# PCB-ARD-MMBOS.net
KiCad netlist of a schematic drawn in EAGLE
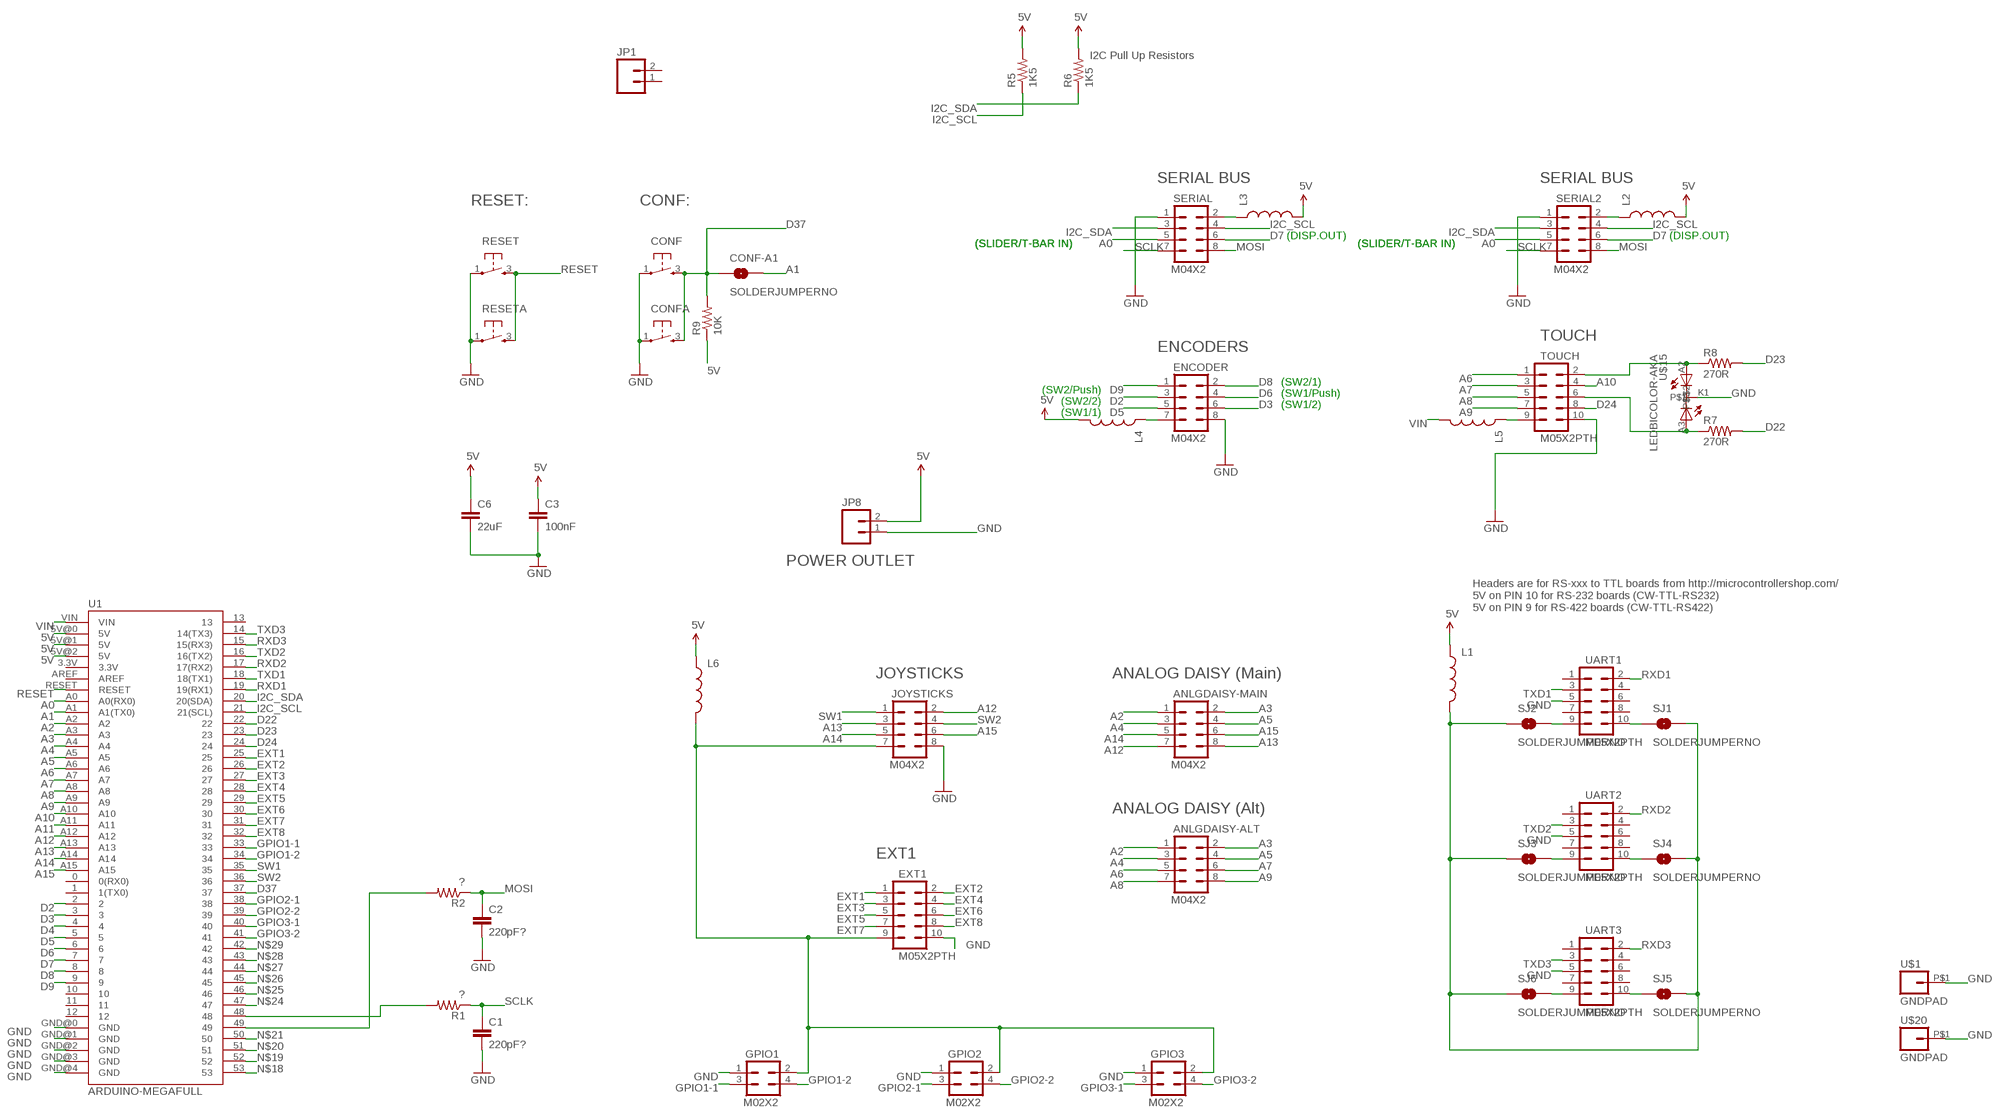
[diagram p0: schematic, sheet 1]

(export (version "E")
  (design (tool "Eeschema 10.0.6"))
  (components
    (comp (ref "ANLGDAISY-ALT")
      (value "M04X2")
      (footprint "eagle-import:2X4")
      (libsource (lib "eagle-import") (part "M04X2"))
    )
    (comp (ref "ANLGDAISY-MAIN")
      (value "M04X2")
      (footprint "eagle-import:2X4")
      (libsource (lib "eagle-import") (part "M04X2"))
    )
    (comp (ref "C1")
      (value "220pF?")
      (footprint "eagle-import:0603-CAP")
      (libsource (lib "eagle-import") (part "CAP0603-CAP"))
    )
    (comp (ref "C2")
      (value "220pF?")
      (footprint "eagle-import:0603-CAP")
      (libsource (lib "eagle-import") (part "CAP0603-CAP"))
    )
    (comp (ref "C3")
      (value "100nF")
      (footprint "eagle-import:0603-CAP")
      (libsource (lib "eagle-import") (part "CAP0603-CAP"))
    )
    (comp (ref "C6")
      (value "22uF")
      (footprint "eagle-import:0805")
      (libsource (lib "eagle-import") (part "CAP0805"))
    )
    (comp (ref "CONF")
      (value "TAC_SWITCH")
      (footprint "eagle-import:PUSHBUTTON")
      (libsource (lib "eagle-import") (part "TAC_SWITCH"))
    )
    (comp (ref "CONF-A1")
      (value "SOLDERJUMPERNO")
      (footprint "eagle-import:SJ_2S-NO")
      (libsource (lib "eagle-import") (part "SOLDERJUMPERNO"))
    )
    (comp (ref "CONFA")
      (value "TAC_SWITCH")
      (footprint "eagle-import:PUSHBUTTON")
      (libsource (lib "eagle-import") (part "TAC_SWITCH"))
    )
    (comp (ref "ENCODER")
      (value "M04X2")
      (footprint "eagle-import:2X4")
      (libsource (lib "eagle-import") (part "M04X2"))
    )
    (comp (ref "EXT1")
      (value "M05X2PTH")
      (footprint "eagle-import:AVR_ICSP")
      (libsource (lib "eagle-import") (part "M05X2PTH"))
    )
    (comp (ref "GPIO1")
      (value "M02X2")
      (footprint "eagle-import:2X2")
      (libsource (lib "eagle-import") (part "M02X2"))
    )
    (comp (ref "GPIO2")
      (value "M02X2")
      (footprint "eagle-import:2X2")
      (libsource (lib "eagle-import") (part "M02X2"))
    )
    (comp (ref "GPIO3")
      (value "M02X2")
      (footprint "eagle-import:2X2")
      (libsource (lib "eagle-import") (part "M02X2"))
    )
    (comp (ref "JOYSTICKS")
      (value "M04X2")
      (footprint "eagle-import:2X4")
      (libsource (lib "eagle-import") (part "M04X2"))
    )
    (comp (ref "JP1")
      (value "M02PTH")
      (footprint "eagle-import:1X02")
      (libsource (lib "eagle-import") (part "M02PTH"))
    )
    (comp (ref "JP8")
      (value "M02PTH4")
      (footprint "eagle-import:1X02_XTRA_BIG")
      (libsource (lib "eagle-import") (part "M02PTH4"))
    )
    (comp (ref "L1")
      (value "INDUCTOR0805")
      (footprint "eagle-import:0805")
      (libsource (lib "eagle-import") (part "INDUCTOR0805"))
    )
    (comp (ref "L2")
      (value "INDUCTOR0805")
      (footprint "eagle-import:0805")
      (libsource (lib "eagle-import") (part "INDUCTOR0805"))
    )
    (comp (ref "L3")
      (value "INDUCTOR0805")
      (footprint "eagle-import:0805")
      (libsource (lib "eagle-import") (part "INDUCTOR0805"))
    )
    (comp (ref "L4")
      (value "INDUCTOR0805")
      (footprint "eagle-import:0805")
      (libsource (lib "eagle-import") (part "INDUCTOR0805"))
    )
    (comp (ref "L5")
      (value "INDUCTOR0805")
      (footprint "eagle-import:0805")
      (libsource (lib "eagle-import") (part "INDUCTOR0805"))
    )
    (comp (ref "L6")
      (value "INDUCTOR0805")
      (footprint "eagle-import:0805")
      (libsource (lib "eagle-import") (part "INDUCTOR0805"))
    )
    (comp (ref "R1")
      (value "?")
      (footprint "eagle-import:0603-RES")
      (libsource (lib "eagle-import") (part "RESISTOR0603-RES"))
    )
    (comp (ref "R2")
      (value "?")
      (footprint "eagle-import:0603-RES")
      (libsource (lib "eagle-import") (part "RESISTOR0603-RES"))
    )
    (comp (ref "R5")
      (value "1K5")
      (footprint "eagle-import:0603-RES")
      (libsource (lib "eagle-import") (part "RESISTOR0603-RES"))
    )
    (comp (ref "R6")
      (value "1K5")
      (footprint "eagle-import:0603-RES")
      (libsource (lib "eagle-import") (part "RESISTOR0603-RES"))
    )
    (comp (ref "R7")
      (value "270R")
      (footprint "eagle-import:0603-RES")
      (libsource (lib "eagle-import") (part "RESISTOR0603-RES"))
    )
    (comp (ref "R8")
      (value "270R")
      (footprint "eagle-import:0603-RES")
      (libsource (lib "eagle-import") (part "RESISTOR0603-RES"))
    )
    (comp (ref "R9")
      (value "10K")
      (footprint "eagle-import:0603-RES")
      (libsource (lib "eagle-import") (part "RESISTOR0603-RES"))
    )
    (comp (ref "RESET")
      (value "TAC_SWITCH")
      (footprint "eagle-import:PUSHBUTTON")
      (libsource (lib "eagle-import") (part "TAC_SWITCH"))
    )
    (comp (ref "RESETA")
      (value "TAC_SWITCH")
      (footprint "eagle-import:PUSHBUTTON")
      (libsource (lib "eagle-import") (part "TAC_SWITCH"))
    )
    (comp (ref "SERIAL")
      (value "M04X2")
      (footprint "eagle-import:2X4")
      (libsource (lib "eagle-import") (part "M04X2"))
    )
    (comp (ref "SERIAL2")
      (value "M04X2")
      (footprint "eagle-import:2X4")
      (libsource (lib "eagle-import") (part "M04X2"))
    )
    (comp (ref "SJ1")
      (value "SOLDERJUMPERNO")
      (footprint "eagle-import:SJ_2S-NO")
      (libsource (lib "eagle-import") (part "SOLDERJUMPERNO"))
    )
    (comp (ref "SJ2")
      (value "SOLDERJUMPERNO")
      (footprint "eagle-import:SJ_2S-NO")
      (libsource (lib "eagle-import") (part "SOLDERJUMPERNO"))
    )
    (comp (ref "SJ3")
      (value "SOLDERJUMPERNO")
      (footprint "eagle-import:SJ_2S-NO")
      (libsource (lib "eagle-import") (part "SOLDERJUMPERNO"))
    )
    (comp (ref "SJ4")
      (value "SOLDERJUMPERNO")
      (footprint "eagle-import:SJ_2S-NO")
      (libsource (lib "eagle-import") (part "SOLDERJUMPERNO"))
    )
    (comp (ref "SJ5")
      (value "SOLDERJUMPERNO")
      (footprint "eagle-import:SJ_2S-NO")
      (libsource (lib "eagle-import") (part "SOLDERJUMPERNO"))
    )
    (comp (ref "SJ6")
      (value "SOLDERJUMPERNO")
      (footprint "eagle-import:SJ_2S-NO")
      (libsource (lib "eagle-import") (part "SOLDERJUMPERNO"))
    )
    (comp (ref "TOUCH")
      (value "M05X2PTH")
      (footprint "eagle-import:AVR_ICSP")
      (libsource (lib "eagle-import") (part "M05X2PTH"))
    )
    (comp (ref "U$1")
      (value "GNDPAD")
      (footprint "eagle-import:3.2MMPAD")
      (libsource (lib "eagle-import") (part "GNDPAD"))
    )
    (comp (ref "U$15")
      (value "LEDBICOLOR-AKA")
      (footprint "eagle-import:LED5MM-BICOLOR")
      (libsource (lib "eagle-import") (part "LEDBICOLOR-AKA"))
    )
    (comp (ref "U$20")
      (value "GNDPAD")
      (footprint "eagle-import:3.2MMPAD")
      (libsource (lib "eagle-import") (part "GNDPAD"))
    )
    (comp (ref "U1")
      (value "ARDUINO-MEGAFULL")
      (footprint "eagle-import:ARDUINO_MEGA")
      (libsource (lib "eagle-import") (part "ARDUINO-MEGAFULL"))
    )
    (comp (ref "UART1")
      (value "M05X2PTH")
      (footprint "eagle-import:AVR_ICSP")
      (libsource (lib "eagle-import") (part "M05X2PTH"))
    )
    (comp (ref "UART2")
      (value "M05X2PTH")
      (footprint "eagle-import:AVR_ICSP")
      (libsource (lib "eagle-import") (part "M05X2PTH"))
    )
    (comp (ref "UART3")
      (value "M05X2PTH")
      (footprint "eagle-import:AVR_ICSP")
      (libsource (lib "eagle-import") (part "M05X2PTH"))
    )
  )
  (nets
    (net (code "1") (name "/A0") (class "Default")
      (node (ref "SERIAL") (pin "5") (pinfunction "5_5") (pintype "passive"))
      (node (ref "SERIAL2") (pin "5") (pinfunction "5_5") (pintype "passive"))
      (node (ref "U1") (pin "A0") (pinfunction "A0(RX0)_A0") (pintype "bidirectional"))
    )
    (net (code "2") (name "/A1") (class "Default")
      (node (ref "CONF-A1") (pin "2") (pinfunction "2_2") (pintype "passive"))
      (node (ref "U1") (pin "A1") (pinfunction "A1(TX0)_A1") (pintype "bidirectional"))
    )
    (net (code "3") (name "/A2") (class "Default")
      (node (ref "ANLGDAISY-ALT") (pin "1") (pinfunction "1_1") (pintype "passive"))
      (node (ref "ANLGDAISY-MAIN") (pin "1") (pinfunction "1_1") (pintype "passive"))
      (node (ref "U1") (pin "A2") (pinfunction "A2_A2") (pintype "bidirectional"))
    )
    (net (code "4") (name "/A3") (class "Default")
      (node (ref "ANLGDAISY-ALT") (pin "2") (pinfunction "2_2") (pintype "passive"))
      (node (ref "ANLGDAISY-MAIN") (pin "2") (pinfunction "2_2") (pintype "passive"))
      (node (ref "U1") (pin "A3") (pinfunction "A3_A3") (pintype "bidirectional"))
    )
    (net (code "5") (name "/A4") (class "Default")
      (node (ref "ANLGDAISY-ALT") (pin "3") (pinfunction "3_3") (pintype "passive"))
      (node (ref "ANLGDAISY-MAIN") (pin "3") (pinfunction "3_3") (pintype "passive"))
      (node (ref "U1") (pin "A4") (pinfunction "A4_A4") (pintype "bidirectional"))
    )
    (net (code "6") (name "/A5") (class "Default")
      (node (ref "ANLGDAISY-ALT") (pin "4") (pinfunction "4_4") (pintype "passive"))
      (node (ref "ANLGDAISY-MAIN") (pin "4") (pinfunction "4_4") (pintype "passive"))
      (node (ref "U1") (pin "A5") (pinfunction "A5_A5") (pintype "bidirectional"))
    )
    (net (code "7") (name "/A6") (class "Default")
      (node (ref "ANLGDAISY-ALT") (pin "5") (pinfunction "5_5") (pintype "passive"))
      (node (ref "TOUCH") (pin "1") (pinfunction "1_1") (pintype "passive"))
      (node (ref "U1") (pin "A6") (pinfunction "A6_A6") (pintype "bidirectional"))
    )
    (net (code "8") (name "/A7") (class "Default")
      (node (ref "ANLGDAISY-ALT") (pin "6") (pinfunction "6_6") (pintype "passive"))
      (node (ref "TOUCH") (pin "3") (pinfunction "3_3") (pintype "passive"))
      (node (ref "U1") (pin "A7") (pinfunction "A7_A7") (pintype "bidirectional"))
    )
    (net (code "9") (name "/A8") (class "Default")
      (node (ref "ANLGDAISY-ALT") (pin "7") (pinfunction "7_7") (pintype "passive"))
      (node (ref "TOUCH") (pin "5") (pinfunction "5_5") (pintype "passive"))
      (node (ref "U1") (pin "A8") (pinfunction "A8_A8") (pintype "bidirectional"))
    )
    (net (code "10") (name "/A9") (class "Default")
      (node (ref "ANLGDAISY-ALT") (pin "8") (pinfunction "8_8") (pintype "passive"))
      (node (ref "TOUCH") (pin "7") (pinfunction "7_7") (pintype "passive"))
      (node (ref "U1") (pin "A9") (pinfunction "A9_A9") (pintype "bidirectional"))
    )
    (net (code "11") (name "/A10") (class "Default")
      (node (ref "TOUCH") (pin "4") (pinfunction "4_4") (pintype "passive"))
      (node (ref "U1") (pin "A10") (pinfunction "A10_A10") (pintype "bidirectional"))
    )
    (net (code "12") (name "/A11") (class "Default")
      (node (ref "U1") (pin "A11") (pinfunction "A11_A11") (pintype "bidirectional"))
    )
    (net (code "13") (name "/A12") (class "Default")
      (node (ref "ANLGDAISY-MAIN") (pin "7") (pinfunction "7_7") (pintype "passive"))
      (node (ref "JOYSTICKS") (pin "2") (pinfunction "2_2") (pintype "passive"))
      (node (ref "U1") (pin "A12") (pinfunction "A12_A12") (pintype "bidirectional"))
    )
    (net (code "14") (name "/A13") (class "Default")
      (node (ref "ANLGDAISY-MAIN") (pin "8") (pinfunction "8_8") (pintype "passive"))
      (node (ref "JOYSTICKS") (pin "3") (pinfunction "3_3") (pintype "passive"))
      (node (ref "U1") (pin "A13") (pinfunction "A13_A13") (pintype "bidirectional"))
    )
    (net (code "15") (name "/A14") (class "Default")
      (node (ref "ANLGDAISY-MAIN") (pin "5") (pinfunction "5_5") (pintype "passive"))
      (node (ref "JOYSTICKS") (pin "5") (pinfunction "5_5") (pintype "passive"))
      (node (ref "U1") (pin "A14") (pinfunction "A14_A14") (pintype "bidirectional"))
    )
    (net (code "16") (name "/A15") (class "Default")
      (node (ref "ANLGDAISY-MAIN") (pin "6") (pinfunction "6_6") (pintype "passive"))
      (node (ref "JOYSTICKS") (pin "6") (pinfunction "6_6") (pintype "passive"))
      (node (ref "U1") (pin "A15") (pinfunction "A15_A15") (pintype "bidirectional"))
    )
    (net (code "17") (name "/D2") (class "Default")
      (node (ref "ENCODER") (pin "3") (pinfunction "3_3") (pintype "passive"))
      (node (ref "U1") (pin "2") (pinfunction "2_2") (pintype "bidirectional"))
    )
    (net (code "18") (name "/D3") (class "Default")
      (node (ref "ENCODER") (pin "6") (pinfunction "6_6") (pintype "passive"))
      (node (ref "U1") (pin "3") (pinfunction "3_3") (pintype "bidirectional"))
    )
    (net (code "19") (name "/D4") (class "Default")
      (node (ref "U1") (pin "4") (pinfunction "4_4") (pintype "bidirectional"))
    )
    (net (code "20") (name "/D5") (class "Default")
      (node (ref "ENCODER") (pin "5") (pinfunction "5_5") (pintype "passive"))
      (node (ref "U1") (pin "5") (pinfunction "5_5") (pintype "bidirectional"))
    )
    (net (code "21") (name "/D6") (class "Default")
      (node (ref "ENCODER") (pin "4") (pinfunction "4_4") (pintype "passive"))
      (node (ref "U1") (pin "6") (pinfunction "6_6") (pintype "bidirectional"))
    )
    (net (code "22") (name "/D7") (class "Default")
      (node (ref "SERIAL") (pin "6") (pinfunction "6_6") (pintype "passive"))
      (node (ref "SERIAL2") (pin "6") (pinfunction "6_6") (pintype "passive"))
      (node (ref "U1") (pin "7") (pinfunction "7_7") (pintype "bidirectional"))
    )
    (net (code "23") (name "/D8") (class "Default")
      (node (ref "ENCODER") (pin "2") (pinfunction "2_2") (pintype "passive"))
      (node (ref "U1") (pin "8") (pinfunction "8_8") (pintype "bidirectional"))
    )
    (net (code "24") (name "/D9") (class "Default")
      (node (ref "ENCODER") (pin "1") (pinfunction "1_1") (pintype "passive"))
      (node (ref "U1") (pin "9") (pinfunction "9_9") (pintype "bidirectional"))
    )
    (net (code "25") (name "/D22") (class "Default")
      (node (ref "R7") (pin "2") (pinfunction "2_2") (pintype "passive"))
      (node (ref "U1") (pin "22") (pinfunction "22_22") (pintype "bidirectional"))
    )
    (net (code "26") (name "/D23") (class "Default")
      (node (ref "R8") (pin "2") (pinfunction "2_2") (pintype "passive"))
      (node (ref "U1") (pin "23") (pinfunction "23_23") (pintype "bidirectional"))
    )
    (net (code "27") (name "/D24") (class "Default")
      (node (ref "TOUCH") (pin "8") (pinfunction "8_8") (pintype "passive"))
      (node (ref "U1") (pin "24") (pinfunction "24_24") (pintype "bidirectional"))
    )
    (net (code "28") (name "/D37") (class "Default")
      (node (ref "CONF") (pin "3") (pinfunction "3_3") (pintype "passive"))
      (node (ref "CONF-A1") (pin "1") (pinfunction "1_1") (pintype "passive"))
      (node (ref "CONFA") (pin "3") (pinfunction "3_3") (pintype "passive"))
      (node (ref "R9") (pin "2") (pinfunction "2_2") (pintype "passive"))
      (node (ref "U1") (pin "37") (pinfunction "37_37") (pintype "bidirectional"))
    )
    (net (code "29") (name "/EXT1") (class "Default")
      (node (ref "EXT1") (pin "1") (pinfunction "1_1") (pintype "passive"))
      (node (ref "U1") (pin "25") (pinfunction "25_25") (pintype "bidirectional"))
    )
    (net (code "30") (name "/EXT2") (class "Default")
      (node (ref "EXT1") (pin "2") (pinfunction "2_2") (pintype "passive"))
      (node (ref "U1") (pin "26") (pinfunction "26_26") (pintype "bidirectional"))
    )
    (net (code "31") (name "/EXT3") (class "Default")
      (node (ref "EXT1") (pin "3") (pinfunction "3_3") (pintype "passive"))
      (node (ref "U1") (pin "27") (pinfunction "27_27") (pintype "bidirectional"))
    )
    (net (code "32") (name "/EXT4") (class "Default")
      (node (ref "EXT1") (pin "4") (pinfunction "4_4") (pintype "passive"))
      (node (ref "U1") (pin "28") (pinfunction "28_28") (pintype "bidirectional"))
    )
    (net (code "33") (name "/EXT5") (class "Default")
      (node (ref "EXT1") (pin "5") (pinfunction "5_5") (pintype "passive"))
      (node (ref "U1") (pin "29") (pinfunction "29_29") (pintype "bidirectional"))
    )
    (net (code "34") (name "/EXT6") (class "Default")
      (node (ref "EXT1") (pin "6") (pinfunction "6_6") (pintype "passive"))
      (node (ref "U1") (pin "30") (pinfunction "30_30") (pintype "bidirectional"))
    )
    (net (code "35") (name "/EXT7") (class "Default")
      (node (ref "EXT1") (pin "7") (pinfunction "7_7") (pintype "passive"))
      (node (ref "U1") (pin "31") (pinfunction "31_31") (pintype "bidirectional"))
    )
    (net (code "36") (name "/EXT8") (class "Default")
      (node (ref "EXT1") (pin "8") (pinfunction "8_8") (pintype "passive"))
      (node (ref "U1") (pin "32") (pinfunction "32_32") (pintype "bidirectional"))
    )
    (net (code "37") (name "/GPIO1-1") (class "Default")
      (node (ref "GPIO1") (pin "3") (pinfunction "3_3") (pintype "passive"))
      (node (ref "U1") (pin "33") (pinfunction "33_33") (pintype "bidirectional"))
    )
    (net (code "38") (name "/GPIO1-2") (class "Default")
      (node (ref "GPIO1") (pin "4") (pinfunction "4_4") (pintype "passive"))
      (node (ref "U1") (pin "34") (pinfunction "34_34") (pintype "bidirectional"))
    )
    (net (code "39") (name "/GPIO2-1") (class "Default")
      (node (ref "GPIO2") (pin "3") (pinfunction "3_3") (pintype "passive"))
      (node (ref "U1") (pin "38") (pinfunction "38_38") (pintype "bidirectional"))
    )
    (net (code "40") (name "/GPIO2-2") (class "Default")
      (node (ref "GPIO2") (pin "4") (pinfunction "4_4") (pintype "passive"))
      (node (ref "U1") (pin "39") (pinfunction "39_39") (pintype "bidirectional"))
    )
    (net (code "41") (name "/GPIO3-1") (class "Default")
      (node (ref "GPIO3") (pin "3") (pinfunction "3_3") (pintype "passive"))
      (node (ref "U1") (pin "40") (pinfunction "40_40") (pintype "bidirectional"))
    )
    (net (code "42") (name "/GPIO3-2") (class "Default")
      (node (ref "GPIO3") (pin "4") (pinfunction "4_4") (pintype "passive"))
      (node (ref "U1") (pin "41") (pinfunction "41_41") (pintype "bidirectional"))
    )
    (net (code "43") (name "/I2C_SCL") (class "Default")
      (node (ref "R5") (pin "1") (pinfunction "1_1") (pintype "passive"))
      (node (ref "SERIAL") (pin "4") (pinfunction "4_4") (pintype "passive"))
      (node (ref "SERIAL2") (pin "4") (pinfunction "4_4") (pintype "passive"))
      (node (ref "U1") (pin "21") (pinfunction "21(SCL)_21") (pintype "bidirectional"))
    )
    (net (code "44") (name "/I2C_SDA") (class "Default")
      (node (ref "R6") (pin "1") (pinfunction "1_1") (pintype "passive"))
      (node (ref "SERIAL") (pin "3") (pinfunction "3_3") (pintype "passive"))
      (node (ref "SERIAL2") (pin "3") (pinfunction "3_3") (pintype "passive"))
      (node (ref "U1") (pin "20") (pinfunction "20(SDA)_20") (pintype "bidirectional"))
    )
    (net (code "45") (name "/MOSI") (class "Default")
      (node (ref "C2") (pin "1") (pinfunction "1_1") (pintype "passive"))
      (node (ref "R2") (pin "1") (pinfunction "1_1") (pintype "passive"))
      (node (ref "SERIAL") (pin "8") (pinfunction "8_8") (pintype "passive"))
      (node (ref "SERIAL2") (pin "8") (pinfunction "8_8") (pintype "passive"))
    )
    (net (code "46") (name "/N$18") (class "Default")
      (node (ref "U1") (pin "53") (pinfunction "53_53") (pintype "bidirectional"))
    )
    (net (code "47") (name "/N$19") (class "Default")
      (node (ref "U1") (pin "52") (pinfunction "52_52") (pintype "bidirectional"))
    )
    (net (code "48") (name "/N$20") (class "Default")
      (node (ref "U1") (pin "51") (pinfunction "51_51") (pintype "bidirectional"))
    )
    (net (code "49") (name "/N$21") (class "Default")
      (node (ref "U1") (pin "50") (pinfunction "50_50") (pintype "bidirectional"))
    )
    (net (code "50") (name "/N$24") (class "Default")
      (node (ref "U1") (pin "47") (pinfunction "47_47") (pintype "bidirectional"))
    )
    (net (code "51") (name "/N$25") (class "Default")
      (node (ref "U1") (pin "46") (pinfunction "46_46") (pintype "bidirectional"))
    )
    (net (code "52") (name "/N$26") (class "Default")
      (node (ref "U1") (pin "45") (pinfunction "45_45") (pintype "bidirectional"))
    )
    (net (code "53") (name "/N$27") (class "Default")
      (node (ref "U1") (pin "44") (pinfunction "44_44") (pintype "bidirectional"))
    )
    (net (code "54") (name "/N$28") (class "Default")
      (node (ref "U1") (pin "43") (pinfunction "43_43") (pintype "bidirectional"))
    )
    (net (code "55") (name "/N$29") (class "Default")
      (node (ref "U1") (pin "42") (pinfunction "42_42") (pintype "bidirectional"))
    )
    (net (code "56") (name "/RESET") (class "Default")
      (node (ref "RESET") (pin "3") (pinfunction "3_3") (pintype "passive"))
      (node (ref "RESETA") (pin "3") (pinfunction "3_3") (pintype "passive"))
      (node (ref "U1") (pin "RESET") (pinfunction "RESET_RESET") (pintype "bidirectional"))
    )
    (net (code "57") (name "/RXD1") (class "Default")
      (node (ref "U1") (pin "19") (pinfunction "19(RX1)_19") (pintype "bidirectional"))
      (node (ref "UART1") (pin "2") (pinfunction "2_2") (pintype "passive"))
    )
    (net (code "58") (name "/RXD2") (class "Default")
      (node (ref "U1") (pin "17") (pinfunction "17(RX2)_17") (pintype "bidirectional"))
      (node (ref "UART2") (pin "2") (pinfunction "2_2") (pintype "passive"))
    )
    (net (code "59") (name "/RXD3") (class "Default")
      (node (ref "U1") (pin "15") (pinfunction "15(RX3)_15") (pintype "bidirectional"))
      (node (ref "UART3") (pin "2") (pinfunction "2_2") (pintype "passive"))
    )
    (net (code "60") (name "/SCLK") (class "Default")
      (node (ref "C1") (pin "1") (pinfunction "1_1") (pintype "passive"))
      (node (ref "R1") (pin "1") (pinfunction "1_1") (pintype "passive"))
      (node (ref "SERIAL") (pin "7") (pinfunction "7_7") (pintype "passive"))
      (node (ref "SERIAL2") (pin "7") (pinfunction "7_7") (pintype "passive"))
    )
    (net (code "61") (name "/SW1") (class "Default")
      (node (ref "JOYSTICKS") (pin "1") (pinfunction "1_1") (pintype "passive"))
      (node (ref "U1") (pin "35") (pinfunction "35_35") (pintype "bidirectional"))
    )
    (net (code "62") (name "/SW2") (class "Default")
      (node (ref "JOYSTICKS") (pin "4") (pinfunction "4_4") (pintype "passive"))
      (node (ref "U1") (pin "36") (pinfunction "36_36") (pintype "bidirectional"))
    )
    (net (code "63") (name "/TXD1") (class "Default")
      (node (ref "U1") (pin "18") (pinfunction "18(TX1)_18") (pintype "bidirectional"))
      (node (ref "UART1") (pin "3") (pinfunction "3_3") (pintype "passive"))
    )
    (net (code "64") (name "/TXD2") (class "Default")
      (node (ref "U1") (pin "16") (pinfunction "16(TX2)_16") (pintype "bidirectional"))
      (node (ref "UART2") (pin "3") (pinfunction "3_3") (pintype "passive"))
    )
    (net (code "65") (name "/TXD3") (class "Default")
      (node (ref "U1") (pin "14") (pinfunction "14(TX3)_14") (pintype "bidirectional"))
      (node (ref "UART3") (pin "3") (pinfunction "3_3") (pintype "passive"))
    )
    (net (code "66") (name "/VIN") (class "Default")
      (node (ref "L5") (pin "2") (pinfunction "2_2") (pintype "passive"))
      (node (ref "U1") (pin "VIN") (pinfunction "VIN_VIN") (pintype "bidirectional"))
    )
    (net (code "67") (name "5V") (class "Default")
      (node (ref "C3") (pin "1") (pinfunction "1_1") (pintype "passive"))
      (node (ref "C6") (pin "1") (pinfunction "1_1") (pintype "passive"))
      (node (ref "JP8") (pin "2") (pinfunction "2_2") (pintype "passive"))
      (node (ref "L1") (pin "1") (pinfunction "1_1") (pintype "passive"))
      (node (ref "L2") (pin "2") (pinfunction "2_2") (pintype "passive"))
      (node (ref "L3") (pin "2") (pinfunction "2_2") (pintype "passive"))
      (node (ref "L4") (pin "2") (pinfunction "2_2") (pintype "passive"))
      (node (ref "L6") (pin "1") (pinfunction "1_1") (pintype "passive"))
      (node (ref "R5") (pin "2") (pinfunction "2_2") (pintype "passive"))
      (node (ref "R6") (pin "2") (pinfunction "2_2") (pintype "passive"))
      (node (ref "R9") (pin "1") (pinfunction "1_1") (pintype "passive"))
      (node (ref "U1") (pin "5V@0") (pinfunction "5V_5V@0") (pintype "bidirectional"))
      (node (ref "U1") (pin "5V@1") (pinfunction "5V_5V@1") (pintype "bidirectional"))
      (node (ref "U1") (pin "5V@2") (pinfunction "5V_5V@2") (pintype "bidirectional"))
    )
    (net (code "68") (name "GND") (class "Default")
      (node (ref "C1") (pin "2") (pinfunction "2_2") (pintype "passive"))
      (node (ref "C2") (pin "2") (pinfunction "2_2") (pintype "passive"))
      (node (ref "C3") (pin "2") (pinfunction "2_2") (pintype "passive"))
      (node (ref "C6") (pin "2") (pinfunction "2_2") (pintype "passive"))
      (node (ref "CONF") (pin "1") (pinfunction "1_1") (pintype "passive"))
      (node (ref "CONFA") (pin "1") (pinfunction "1_1") (pintype "passive"))
      (node (ref "ENCODER") (pin "8") (pinfunction "8_8") (pintype "passive"))
      (node (ref "EXT1") (pin "10") (pinfunction "10_10") (pintype "passive"))
      (node (ref "GPIO1") (pin "1") (pinfunction "1_1") (pintype "passive"))
      (node (ref "GPIO2") (pin "1") (pinfunction "1_1") (pintype "passive"))
      (node (ref "GPIO3") (pin "1") (pinfunction "1_1") (pintype "passive"))
      (node (ref "JOYSTICKS") (pin "8") (pinfunction "8_8") (pintype "passive"))
      (node (ref "JP8") (pin "1") (pinfunction "1_1") (pintype "passive"))
      (node (ref "RESET") (pin "1") (pinfunction "1_1") (pintype "passive"))
      (node (ref "RESETA") (pin "1") (pinfunction "1_1") (pintype "passive"))
      (node (ref "SERIAL") (pin "1") (pinfunction "1_1") (pintype "passive"))
      (node (ref "SERIAL2") (pin "1") (pinfunction "1_1") (pintype "passive"))
      (node (ref "TOUCH") (pin "10") (pinfunction "10_10") (pintype "passive"))
      (node (ref "U$1") (pin "P$1") (pinfunction "1_P$1") (pintype "passive"))
      (node (ref "U$15") (pin "K1") (pinfunction "P$1_K1") (pintype "bidirectional"))
      (node (ref "U$20") (pin "P$1") (pinfunction "1_P$1") (pintype "passive"))
      (node (ref "U1") (pin "GND@0") (pinfunction "GND_GND@0") (pintype "bidirectional"))
      (node (ref "U1") (pin "GND@1") (pinfunction "GND_GND@1") (pintype "bidirectional"))
      (node (ref "U1") (pin "GND@2") (pinfunction "GND_GND@2") (pintype "bidirectional"))
      (node (ref "U1") (pin "GND@3") (pinfunction "GND_GND@3") (pintype "bidirectional"))
      (node (ref "U1") (pin "GND@4") (pinfunction "GND_GND@4") (pintype "bidirectional"))
      (node (ref "UART1") (pin "5") (pinfunction "5_5") (pintype "passive"))
      (node (ref "UART2") (pin "5") (pinfunction "5_5") (pintype "passive"))
      (node (ref "UART3") (pin "5") (pinfunction "5_5") (pintype "passive"))
    )
    (net (code "69") (name "Net-(ENCODER-Pad7)") (class "Default")
      (node (ref "ENCODER") (pin "7") (pinfunction "7_7") (pintype "passive"))
      (node (ref "L4") (pin "1") (pinfunction "1_1") (pintype "passive"))
    )
    (net (code "70") (name "Net-(EXT1-Pad9)") (class "Default")
      (node (ref "EXT1") (pin "9") (pinfunction "9_9") (pintype "passive"))
      (node (ref "GPIO1") (pin "2") (pinfunction "2_2") (pintype "passive"))
      (node (ref "GPIO2") (pin "2") (pinfunction "2_2") (pintype "passive"))
      (node (ref "GPIO3") (pin "2") (pinfunction "2_2") (pintype "passive"))
      (node (ref "JOYSTICKS") (pin "7") (pinfunction "7_7") (pintype "passive"))
      (node (ref "L6") (pin "2") (pinfunction "2_2") (pintype "passive"))
    )
    (net (code "71") (name "Net-(L1-Pad2)") (class "Default")
      (node (ref "L1") (pin "2") (pinfunction "2_2") (pintype "passive"))
      (node (ref "SJ1") (pin "2") (pinfunction "2_2") (pintype "passive"))
      (node (ref "SJ2") (pin "1") (pinfunction "1_1") (pintype "passive"))
      (node (ref "SJ3") (pin "1") (pinfunction "1_1") (pintype "passive"))
      (node (ref "SJ4") (pin "2") (pinfunction "2_2") (pintype "passive"))
      (node (ref "SJ5") (pin "2") (pinfunction "2_2") (pintype "passive"))
      (node (ref "SJ6") (pin "1") (pinfunction "1_1") (pintype "passive"))
    )
    (net (code "72") (name "Net-(L2-Pad1)") (class "Default")
      (node (ref "L2") (pin "1") (pinfunction "1_1") (pintype "passive"))
      (node (ref "SERIAL2") (pin "2") (pinfunction "2_2") (pintype "passive"))
    )
    (net (code "73") (name "Net-(L3-Pad1)") (class "Default")
      (node (ref "L3") (pin "1") (pinfunction "1_1") (pintype "passive"))
      (node (ref "SERIAL") (pin "2") (pinfunction "2_2") (pintype "passive"))
    )
    (net (code "74") (name "Net-(L5-Pad1)") (class "Default")
      (node (ref "L5") (pin "1") (pinfunction "1_1") (pintype "passive"))
      (node (ref "TOUCH") (pin "9") (pinfunction "9_9") (pintype "passive"))
    )
    (net (code "75") (name "Net-(R1-Pad2)") (class "Default")
      (node (ref "R1") (pin "2") (pinfunction "2_2") (pintype "passive"))
      (node (ref "U1") (pin "48") (pinfunction "48_48") (pintype "bidirectional"))
    )
    (net (code "76") (name "Net-(R2-Pad2)") (class "Default")
      (node (ref "R2") (pin "2") (pinfunction "2_2") (pintype "passive"))
      (node (ref "U1") (pin "49") (pinfunction "49_49") (pintype "bidirectional"))
    )
    (net (code "77") (name "Net-(SJ1-Pad1)") (class "Default")
      (node (ref "SJ1") (pin "1") (pinfunction "1_1") (pintype "passive"))
      (node (ref "UART1") (pin "10") (pinfunction "10_10") (pintype "passive"))
    )
    (net (code "78") (name "Net-(SJ2-Pad2)") (class "Default")
      (node (ref "SJ2") (pin "2") (pinfunction "2_2") (pintype "passive"))
      (node (ref "UART1") (pin "9") (pinfunction "9_9") (pintype "passive"))
    )
    (net (code "79") (name "Net-(SJ3-Pad2)") (class "Default")
      (node (ref "SJ3") (pin "2") (pinfunction "2_2") (pintype "passive"))
      (node (ref "UART2") (pin "9") (pinfunction "9_9") (pintype "passive"))
    )
    (net (code "80") (name "Net-(SJ4-Pad1)") (class "Default")
      (node (ref "SJ4") (pin "1") (pinfunction "1_1") (pintype "passive"))
      (node (ref "UART2") (pin "10") (pinfunction "10_10") (pintype "passive"))
    )
    (net (code "81") (name "Net-(SJ5-Pad1)") (class "Default")
      (node (ref "SJ5") (pin "1") (pinfunction "1_1") (pintype "passive"))
      (node (ref "UART3") (pin "10") (pinfunction "10_10") (pintype "passive"))
    )
    (net (code "82") (name "Net-(SJ6-Pad2)") (class "Default")
      (node (ref "SJ6") (pin "2") (pinfunction "2_2") (pintype "passive"))
      (node (ref "UART3") (pin "9") (pinfunction "9_9") (pintype "passive"))
    )
    (net (code "83") (name "Net-(U$15-P$2)") (class "Default")
      (node (ref "R8") (pin "1") (pinfunction "1_1") (pintype "passive"))
      (node (ref "TOUCH") (pin "2") (pinfunction "2_2") (pintype "passive"))
      (node (ref "U$15") (pin "A2") (pinfunction "P$2_A2") (pintype "bidirectional"))
    )
    (net (code "84") (name "Net-(U$15-P$3)") (class "Default")
      (node (ref "R7") (pin "1") (pinfunction "1_1") (pintype "passive"))
      (node (ref "TOUCH") (pin "6") (pinfunction "6_6") (pintype "passive"))
      (node (ref "U$15") (pin "A3") (pinfunction "P$3_A3") (pintype "bidirectional"))
    )
    (net (code "85") (name "unconnected-(JP1-Pad1)") (class "Default")
      (node (ref "JP1") (pin "1") (pinfunction "1_1") (pintype "passive"))
    )
    (net (code "86") (name "unconnected-(JP1-Pad2)") (class "Default")
      (node (ref "JP1") (pin "2") (pinfunction "2_2") (pintype "passive"))
    )
    (net (code "87") (name "unconnected-(U1-0(RX0)-Pad0)") (class "Default")
      (node (ref "U1") (pin "0") (pinfunction "0(RX0)_0") (pintype "bidirectional"))
    )
    (net (code "88") (name "unconnected-(U1-1(TX0)-Pad1)") (class "Default")
      (node (ref "U1") (pin "1") (pinfunction "1(TX0)_1") (pintype "bidirectional"))
    )
    (net (code "89") (name "unconnected-(U1-Pad3.3V)") (class "Default")
      (node (ref "U1") (pin "3.3V") (pinfunction "3.3V_3.3V") (pintype "bidirectional"))
    )
    (net (code "90") (name "unconnected-(U1-Pad10)") (class "Default")
      (node (ref "U1") (pin "10") (pinfunction "10_10") (pintype "bidirectional"))
    )
    (net (code "91") (name "unconnected-(U1-Pad11)") (class "Default")
      (node (ref "U1") (pin "11") (pinfunction "11_11") (pintype "bidirectional"))
    )
    (net (code "92") (name "unconnected-(U1-Pad12)") (class "Default")
      (node (ref "U1") (pin "12") (pinfunction "12_12") (pintype "bidirectional"))
    )
    (net (code "93") (name "unconnected-(U1-Pad13)") (class "Default")
      (node (ref "U1") (pin "13") (pinfunction "13_13") (pintype "bidirectional"))
    )
    (net (code "94") (name "unconnected-(U1-PadAREF)") (class "Default")
      (node (ref "U1") (pin "AREF") (pinfunction "AREF_AREF") (pintype "bidirectional"))
    )
    (net (code "95") (name "unconnected-(UART1-Pad1)") (class "Default")
      (node (ref "UART1") (pin "1") (pinfunction "1_1") (pintype "passive"))
    )
    (net (code "96") (name "unconnected-(UART1-Pad4)") (class "Default")
      (node (ref "UART1") (pin "4") (pinfunction "4_4") (pintype "passive"))
    )
    (net (code "97") (name "unconnected-(UART1-Pad6)") (class "Default")
      (node (ref "UART1") (pin "6") (pinfunction "6_6") (pintype "passive"))
    )
    (net (code "98") (name "unconnected-(UART1-Pad7)") (class "Default")
      (node (ref "UART1") (pin "7") (pinfunction "7_7") (pintype "passive"))
    )
    (net (code "99") (name "unconnected-(UART1-Pad8)") (class "Default")
      (node (ref "UART1") (pin "8") (pinfunction "8_8") (pintype "passive"))
    )
    (net (code "100") (name "unconnected-(UART2-Pad1)") (class "Default")
      (node (ref "UART2") (pin "1") (pinfunction "1_1") (pintype "passive"))
    )
    (net (code "101") (name "unconnected-(UART2-Pad4)") (class "Default")
      (node (ref "UART2") (pin "4") (pinfunction "4_4") (pintype "passive"))
    )
    (net (code "102") (name "unconnected-(UART2-Pad6)") (class "Default")
      (node (ref "UART2") (pin "6") (pinfunction "6_6") (pintype "passive"))
    )
    (net (code "103") (name "unconnected-(UART2-Pad7)") (class "Default")
      (node (ref "UART2") (pin "7") (pinfunction "7_7") (pintype "passive"))
    )
    (net (code "104") (name "unconnected-(UART2-Pad8)") (class "Default")
      (node (ref "UART2") (pin "8") (pinfunction "8_8") (pintype "passive"))
    )
    (net (code "105") (name "unconnected-(UART3-Pad1)") (class "Default")
      (node (ref "UART3") (pin "1") (pinfunction "1_1") (pintype "passive"))
    )
    (net (code "106") (name "unconnected-(UART3-Pad4)") (class "Default")
      (node (ref "UART3") (pin "4") (pinfunction "4_4") (pintype "passive"))
    )
    (net (code "107") (name "unconnected-(UART3-Pad6)") (class "Default")
      (node (ref "UART3") (pin "6") (pinfunction "6_6") (pintype "passive"))
    )
    (net (code "108") (name "unconnected-(UART3-Pad7)") (class "Default")
      (node (ref "UART3") (pin "7") (pinfunction "7_7") (pintype "passive"))
    )
    (net (code "109") (name "unconnected-(UART3-Pad8)") (class "Default")
      (node (ref "UART3") (pin "8") (pinfunction "8_8") (pintype "passive"))
    )
  )
)
